# yetisponder_vesp02_2_1.net
KiCad netlist of a schematic drawn in EAGLE
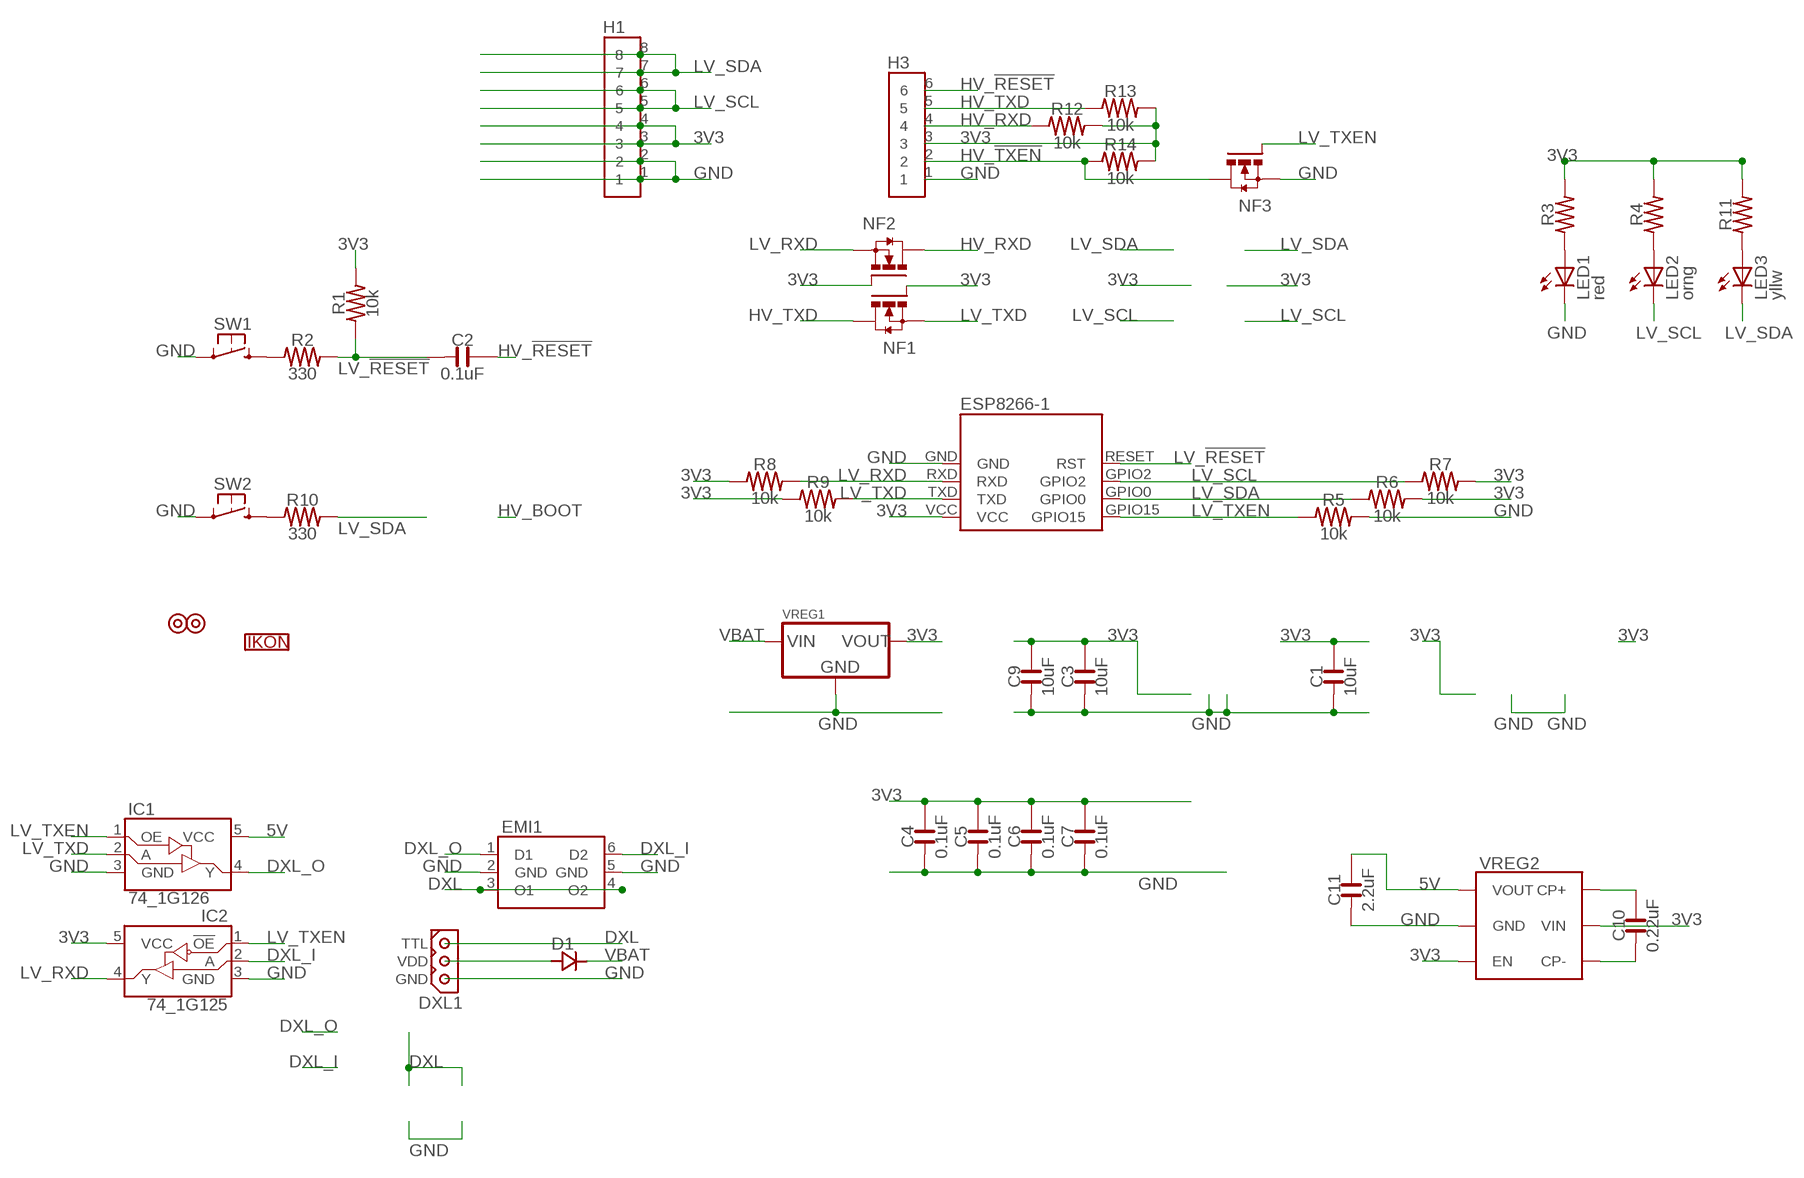
[diagram p0: schematic, sheet 1]

(export (version "E")
  (design (tool "Eeschema 10.0.6"))
  (components
    (comp (ref "C1")
      (value "10uF")
      (footprint "eagle-import:0805_YAGEO")
      (libsource (lib "eagle-import") (part "CAPACITOR-0805"))
    )
    (comp (ref "C2")
      (value "0.1uF")
      (footprint "eagle-import:0402_YAGEO")
      (libsource (lib "eagle-import") (part "CAPACITOR-0402"))
    )
    (comp (ref "C3")
      (value "10uF")
      (footprint "eagle-import:0805_YAGEO")
      (libsource (lib "eagle-import") (part "CAPACITOR-0805"))
    )
    (comp (ref "C4")
      (value "0.1uF")
      (footprint "eagle-import:0402_YAGEO")
      (libsource (lib "eagle-import") (part "CAPACITOR-0402"))
    )
    (comp (ref "C5")
      (value "0.1uF")
      (footprint "eagle-import:0402_YAGEO")
      (libsource (lib "eagle-import") (part "CAPACITOR-0402"))
    )
    (comp (ref "C6")
      (value "0.1uF")
      (footprint "eagle-import:0402_YAGEO")
      (libsource (lib "eagle-import") (part "CAPACITOR-0402"))
    )
    (comp (ref "C7")
      (value "0.1uF")
      (footprint "eagle-import:0402_YAGEO")
      (libsource (lib "eagle-import") (part "CAPACITOR-0402"))
    )
    (comp (ref "C9")
      (value "10uF")
      (footprint "eagle-import:0805_YAGEO")
      (libsource (lib "eagle-import") (part "CAPACITOR-0805"))
    )
    (comp (ref "C10")
      (value "0.22uF")
      (footprint "eagle-import:0402_YAGEO")
      (libsource (lib "eagle-import") (part "CAPACITOR-0402"))
    )
    (comp (ref "C11")
      (value "2.2uF")
      (footprint "eagle-import:0402_YAGEO")
      (libsource (lib "eagle-import") (part "CAPACITOR-0402"))
    )
    (comp (ref "D1")
      (value "DIODE_RECTIFIER-POWER-DI5")
      (footprint "eagle-import:POWER-DI5")
      (libsource (lib "eagle-import") (part "DIODE_RECTIFIER-POWER-DI5"))
    )
    (comp (ref "DXL1")
      (value "DXL_TTL-V")
      (footprint "eagle-import:MOLEX_5267-3")
      (libsource (lib "eagle-import") (part "DXL_TTL-V"))
    )
    (comp (ref "EMI1")
      (value "EMI_2CH")
      (footprint "eagle-import:SOT-563")
      (libsource (lib "eagle-import") (part "EMI_2CH"))
    )
    (comp (ref "ESP8266-1")
      (value "ESP8266-02")
      (footprint "eagle-import:ESP8266-02")
      (libsource (lib "eagle-import") (part "ESP8266-02"))
    )
    (comp (ref "H1")
      (value "HEADER_8P-0.1\"_2X4-SMD-SULLINS")
      (footprint "eagle-import:HEADER-0.1__2X4-SMD-SULLINS")
      (libsource (lib "eagle-import") (part "HEADER_8P-0.1{dblquote}_2X4-SMD-SULLINS"))
    )
    (comp (ref "H3")
      (value "HEADER_6P-0.1\"")
      (footprint "eagle-import:HEADER-0.1__1X6")
      (libsource (lib "eagle-import") (part "HEADER_6P-0.1{dblquote}"))
    )
    (comp (ref "IC1")
      (value "LOGIC_74_1G126-DCK")
      (footprint "eagle-import:DCK(R-PDSO-G5)_SC70")
      (libsource (lib "eagle-import") (part "LOGIC_74_1G126-DCK"))
    )
    (comp (ref "IC2")
      (value "LOGIC_74_1G125-DCK")
      (footprint "eagle-import:DCK(R-PDSO-G5)_SC70")
      (libsource (lib "eagle-import") (part "LOGIC_74_1G125-DCK"))
    )
    (comp (ref "IKON1")
      (value "IKON-VERSACOMA-5")
      (footprint "eagle-import:IKON_VERSACOMA_5MM")
      (libsource (lib "eagle-import") (part "IKON-VERSACOMA-5"))
    )
    (comp (ref "LED1")
      (value "red")
      (footprint "eagle-import:0402_LED")
      (libsource (lib "eagle-import") (part "LED-0402"))
    )
    (comp (ref "LED2")
      (value "orng")
      (footprint "eagle-import:0402_LED")
      (libsource (lib "eagle-import") (part "LED-0402"))
    )
    (comp (ref "LED3")
      (value "yllw")
      (footprint "eagle-import:0402_LED")
      (libsource (lib "eagle-import") (part "LED-0402"))
    )
    (comp (ref "NF1")
      (value "FET_N-CH-SOT-23-3")
      (footprint "eagle-import:SOT-23-3")
      (libsource (lib "eagle-import") (part "FET_N-CH-SOT-23-3"))
    )
    (comp (ref "NF2")
      (value "FET_N-CH-SOT-23-3")
      (footprint "eagle-import:SOT-23-3")
      (libsource (lib "eagle-import") (part "FET_N-CH-SOT-23-3"))
    )
    (comp (ref "NF3")
      (value "FET_N-CH-SOT-23-3")
      (footprint "eagle-import:SOT-23-3")
      (libsource (lib "eagle-import") (part "FET_N-CH-SOT-23-3"))
    )
    (comp (ref "R1")
      (value "10k")
      (footprint "eagle-import:0402_YAGEO")
      (libsource (lib "eagle-import") (part "RESISTOR-0402"))
    )
    (comp (ref "R2")
      (value "330")
      (footprint "eagle-import:0402_YAGEO")
      (libsource (lib "eagle-import") (part "RESISTOR-0402"))
    )
    (comp (ref "R3")
      (value "RESISTOR-0402")
      (footprint "eagle-import:0402_YAGEO")
      (libsource (lib "eagle-import") (part "RESISTOR-0402"))
    )
    (comp (ref "R4")
      (value "RESISTOR-0402")
      (footprint "eagle-import:0402_YAGEO")
      (libsource (lib "eagle-import") (part "RESISTOR-0402"))
    )
    (comp (ref "R5")
      (value "10k")
      (footprint "eagle-import:0402_YAGEO")
      (libsource (lib "eagle-import") (part "RESISTOR-0402"))
    )
    (comp (ref "R6")
      (value "10k")
      (footprint "eagle-import:0402_YAGEO")
      (libsource (lib "eagle-import") (part "RESISTOR-0402"))
    )
    (comp (ref "R7")
      (value "10k")
      (footprint "eagle-import:0402_YAGEO")
      (libsource (lib "eagle-import") (part "RESISTOR-0402"))
    )
    (comp (ref "R8")
      (value "10k")
      (footprint "eagle-import:0402_YAGEO")
      (libsource (lib "eagle-import") (part "RESISTOR-0402"))
    )
    (comp (ref "R9")
      (value "10k")
      (footprint "eagle-import:0402_YAGEO")
      (libsource (lib "eagle-import") (part "RESISTOR-0402"))
    )
    (comp (ref "R10")
      (value "330")
      (footprint "eagle-import:0402_YAGEO")
      (libsource (lib "eagle-import") (part "RESISTOR-0402"))
    )
    (comp (ref "R11")
      (value "RESISTOR-0402")
      (footprint "eagle-import:0402_YAGEO")
      (libsource (lib "eagle-import") (part "RESISTOR-0402"))
    )
    (comp (ref "R12")
      (value "10k")
      (footprint "eagle-import:0402_YAGEO")
      (libsource (lib "eagle-import") (part "RESISTOR-0402"))
    )
    (comp (ref "R13")
      (value "10k")
      (footprint "eagle-import:0402_YAGEO")
      (libsource (lib "eagle-import") (part "RESISTOR-0402"))
    )
    (comp (ref "R14")
      (value "10k")
      (footprint "eagle-import:0402_YAGEO")
      (libsource (lib "eagle-import") (part "RESISTOR-0402"))
    )
    (comp (ref "S1")
      (value "METRIC_SCREWS-M2.5_T")
      (footprint "eagle-import:M2.5_SCREW_TENTED")
      (libsource (lib "eagle-import") (part "METRIC_SCREWS-M2.5_T"))
    )
    (comp (ref "S2")
      (value "METRIC_SCREWS-M2.5_T")
      (footprint "eagle-import:M2.5_SCREW_TENTED")
      (libsource (lib "eagle-import") (part "METRIC_SCREWS-M2.5_T"))
    )
    (comp (ref "SW1")
      (value "SWITCH_SPST-6MMX6MM-PTH")
      (footprint "eagle-import:SWITCH_TE_1825910-7")
      (libsource (lib "eagle-import") (part "SWITCH_SPST-6MMX6MM-PTH"))
    )
    (comp (ref "SW2")
      (value "SWITCH_SPST-6MMX6MM-PTH")
      (footprint "eagle-import:SWITCH_TE_1825910-7")
      (libsource (lib "eagle-import") (part "SWITCH_SPST-6MMX6MM-PTH"))
    )
    (comp (ref "VREG1")
      (value "VREG_78XX-OKI-78SR-H")
      (footprint "eagle-import:VREG-OKI-78SR-H")
      (libsource (lib "eagle-import") (part "VREG_78XX-OKI-78SR-H"))
    )
    (comp (ref "VREG2")
      (value "VREG_REG710XX")
      (footprint "eagle-import:SOT-23-6")
      (libsource (lib "eagle-import") (part "VREG_REG710XX"))
    )
  )
  (nets
    (net (code "1") (name "/3V3") (class "Default")
      (node (ref "C1") (pin "2") (pinfunction "P$2_2") (pintype "passive"))
      (node (ref "C3") (pin "2") (pinfunction "P$2_2") (pintype "passive"))
      (node (ref "C4") (pin "2") (pinfunction "P$2_2") (pintype "passive"))
      (node (ref "C5") (pin "2") (pinfunction "P$2_2") (pintype "passive"))
      (node (ref "C6") (pin "2") (pinfunction "P$2_2") (pintype "passive"))
      (node (ref "C7") (pin "2") (pinfunction "P$2_2") (pintype "passive"))
      (node (ref "C9") (pin "2") (pinfunction "P$2_2") (pintype "passive"))
      (node (ref "ESP8266-1") (pin "VCC") (pinfunction "VCC_VCC") (pintype "bidirectional"))
      (node (ref "H1") (pin "3") (pinfunction "3_3") (pintype "bidirectional"))
      (node (ref "H1") (pin "4") (pinfunction "4_4") (pintype "bidirectional"))
      (node (ref "H3") (pin "3") (pinfunction "3_3") (pintype "bidirectional"))
      (node (ref "IC2") (pin "5") (pinfunction "VCC_5") (pintype "bidirectional"))
      (node (ref "NF1") (pin "1G") (pinfunction "G_1G") (pintype "passive"))
      (node (ref "NF2") (pin "1G") (pinfunction "G_1G") (pintype "passive"))
      (node (ref "R1") (pin "2") (pinfunction "2_2") (pintype "passive"))
      (node (ref "R11") (pin "2") (pinfunction "2_2") (pintype "passive"))
      (node (ref "R12") (pin "2") (pinfunction "2_2") (pintype "passive"))
      (node (ref "R13") (pin "2") (pinfunction "2_2") (pintype "passive"))
      (node (ref "R14") (pin "2") (pinfunction "2_2") (pintype "passive"))
      (node (ref "R3") (pin "2") (pinfunction "2_2") (pintype "passive"))
      (node (ref "R4") (pin "2") (pinfunction "2_2") (pintype "passive"))
      (node (ref "R6") (pin "2") (pinfunction "2_2") (pintype "passive"))
      (node (ref "R7") (pin "2") (pinfunction "2_2") (pintype "passive"))
      (node (ref "R8") (pin "1") (pinfunction "1_1") (pintype "passive"))
      (node (ref "R9") (pin "1") (pinfunction "1_1") (pintype "passive"))
      (node (ref "VREG1") (pin "3") (pinfunction "VOUT_3") (pintype "bidirectional"))
      (node (ref "VREG2") (pin "3") (pinfunction "EN_3") (pintype "bidirectional"))
      (node (ref "VREG2") (pin "5") (pinfunction "VIN_5") (pintype "bidirectional"))
    )
    (net (code "2") (name "/5V") (class "Default")
      (node (ref "C11") (pin "2") (pinfunction "P$2_2") (pintype "passive"))
      (node (ref "IC1") (pin "5") (pinfunction "VCC_5") (pintype "bidirectional"))
      (node (ref "VREG2") (pin "1") (pinfunction "VOUT_1") (pintype "bidirectional"))
    )
    (net (code "3") (name "/DXL") (class "Default")
      (node (ref "DXL1") (pin "1") (pinfunction "TTL_1") (pintype "bidirectional"))
      (node (ref "EMI1") (pin "3") (pinfunction "O1_3") (pintype "bidirectional"))
      (node (ref "EMI1") (pin "4") (pinfunction "O2_4") (pintype "bidirectional"))
    )
    (net (code "4") (name "/DXL_I") (class "Default")
      (node (ref "EMI1") (pin "6") (pinfunction "D2_6") (pintype "bidirectional"))
      (node (ref "IC2") (pin "2") (pinfunction "A_2") (pintype "bidirectional"))
    )
    (net (code "5") (name "/DXL_O") (class "Default")
      (node (ref "EMI1") (pin "1") (pinfunction "D1_1") (pintype "bidirectional"))
      (node (ref "IC1") (pin "4") (pinfunction "Y_4") (pintype "bidirectional"))
    )
    (net (code "6") (name "/GND") (class "Default")
      (node (ref "C1") (pin "1") (pinfunction "P$1_1") (pintype "passive"))
      (node (ref "C11") (pin "1") (pinfunction "P$1_1") (pintype "passive"))
      (node (ref "C3") (pin "1") (pinfunction "P$1_1") (pintype "passive"))
      (node (ref "C4") (pin "1") (pinfunction "P$1_1") (pintype "passive"))
      (node (ref "C5") (pin "1") (pinfunction "P$1_1") (pintype "passive"))
      (node (ref "C6") (pin "1") (pinfunction "P$1_1") (pintype "passive"))
      (node (ref "C7") (pin "1") (pinfunction "P$1_1") (pintype "passive"))
      (node (ref "C9") (pin "1") (pinfunction "P$1_1") (pintype "passive"))
      (node (ref "DXL1") (pin "3") (pinfunction "GND_3") (pintype "bidirectional"))
      (node (ref "EMI1") (pin "2") (pinfunction "GND_2") (pintype "bidirectional"))
      (node (ref "EMI1") (pin "5") (pinfunction "GND_5") (pintype "bidirectional"))
      (node (ref "ESP8266-1") (pin "GND") (pinfunction "GND_GND") (pintype "bidirectional"))
      (node (ref "H1") (pin "1") (pinfunction "1_1") (pintype "bidirectional"))
      (node (ref "H1") (pin "2") (pinfunction "2_2") (pintype "bidirectional"))
      (node (ref "H3") (pin "1") (pinfunction "1_1") (pintype "bidirectional"))
      (node (ref "IC1") (pin "3") (pinfunction "GND_3") (pintype "bidirectional"))
      (node (ref "IC2") (pin "3") (pinfunction "GND_3") (pintype "bidirectional"))
      (node (ref "LED1") (pin "C") (pinfunction "C_C") (pintype "passive"))
      (node (ref "NF3") (pin "2S") (pinfunction "S_2S") (pintype "passive"))
      (node (ref "R5") (pin "2") (pinfunction "2_2") (pintype "passive"))
      (node (ref "SW1") (pin "2@1") (pinfunction "2_2@1") (pintype "passive"))
      (node (ref "SW1") (pin "2@2") (pinfunction "2_2@2") (pintype "passive"))
      (node (ref "SW2") (pin "2@1") (pinfunction "2_2@1") (pintype "passive"))
      (node (ref "SW2") (pin "2@2") (pinfunction "2_2@2") (pintype "passive"))
      (node (ref "VREG1") (pin "2") (pinfunction "GND_2") (pintype "bidirectional"))
      (node (ref "VREG2") (pin "2") (pinfunction "GND_2") (pintype "bidirectional"))
    )
    (net (code "8") (name "/HV_RXD") (class "Default")
      (node (ref "H3") (pin "4") (pinfunction "4_4") (pintype "bidirectional"))
      (node (ref "NF2") (pin "3D") (pinfunction "D_3D") (pintype "passive"))
      (node (ref "R12") (pin "1") (pinfunction "1_1") (pintype "passive"))
    )
    (net (code "9") (name "/HV_TXD") (class "Default")
      (node (ref "H3") (pin "5") (pinfunction "5_5") (pintype "bidirectional"))
      (node (ref "NF1") (pin "3D") (pinfunction "D_3D") (pintype "passive"))
      (node (ref "R13") (pin "1") (pinfunction "1_1") (pintype "passive"))
    )
    (net (code "10") (name "/HV_~{RESET}") (class "Default")
      (node (ref "C2") (pin "2") (pinfunction "P$2_2") (pintype "passive"))
      (node (ref "H3") (pin "6") (pinfunction "6_6") (pintype "bidirectional"))
    )
    (net (code "11") (name "/HV_~{TXEN}") (class "Default")
      (node (ref "H3") (pin "2") (pinfunction "2_2") (pintype "bidirectional"))
      (node (ref "NF3") (pin "3D") (pinfunction "D_3D") (pintype "passive"))
      (node (ref "R14") (pin "1") (pinfunction "1_1") (pintype "passive"))
    )
    (net (code "12") (name "/LV_RXD") (class "Default")
      (node (ref "ESP8266-1") (pin "RXD") (pinfunction "RXD_RXD") (pintype "bidirectional"))
      (node (ref "IC2") (pin "4") (pinfunction "Y_4") (pintype "bidirectional"))
      (node (ref "NF2") (pin "2S") (pinfunction "S_2S") (pintype "passive"))
      (node (ref "R8") (pin "2") (pinfunction "2_2") (pintype "passive"))
    )
    (net (code "13") (name "/LV_SCL") (class "Default")
      (node (ref "ESP8266-1") (pin "GPIO2") (pinfunction "GPIO2_GPIO2") (pintype "bidirectional"))
      (node (ref "H1") (pin "5") (pinfunction "5_5") (pintype "bidirectional"))
      (node (ref "H1") (pin "6") (pinfunction "6_6") (pintype "bidirectional"))
      (node (ref "LED2") (pin "C") (pinfunction "C_C") (pintype "passive"))
      (node (ref "R7") (pin "1") (pinfunction "1_1") (pintype "passive"))
    )
    (net (code "14") (name "/LV_SDA") (class "Default")
      (node (ref "ESP8266-1") (pin "GPIO0") (pinfunction "GPIO0_GPIO0") (pintype "bidirectional"))
      (node (ref "H1") (pin "7") (pinfunction "7_7") (pintype "bidirectional"))
      (node (ref "H1") (pin "8") (pinfunction "8_8") (pintype "bidirectional"))
      (node (ref "LED3") (pin "C") (pinfunction "C_C") (pintype "passive"))
      (node (ref "R10") (pin "2") (pinfunction "2_2") (pintype "passive"))
      (node (ref "R6") (pin "1") (pinfunction "1_1") (pintype "passive"))
    )
    (net (code "15") (name "/LV_TXD") (class "Default")
      (node (ref "ESP8266-1") (pin "TXD") (pinfunction "TXD_TXD") (pintype "bidirectional"))
      (node (ref "IC1") (pin "2") (pinfunction "A_2") (pintype "bidirectional"))
      (node (ref "NF1") (pin "2S") (pinfunction "S_2S") (pintype "passive"))
      (node (ref "R9") (pin "2") (pinfunction "2_2") (pintype "passive"))
    )
    (net (code "16") (name "/LV_TXEN") (class "Default")
      (node (ref "ESP8266-1") (pin "GPIO15") (pinfunction "GPIO15_GPIO15") (pintype "bidirectional"))
      (node (ref "IC1") (pin "1") (pinfunction "OE_1") (pintype "bidirectional"))
      (node (ref "IC2") (pin "1") (pinfunction "~{OE}_1") (pintype "bidirectional"))
      (node (ref "NF3") (pin "1G") (pinfunction "G_1G") (pintype "passive"))
      (node (ref "R5") (pin "1") (pinfunction "1_1") (pintype "passive"))
    )
    (net (code "17") (name "/LV_~{RESET}") (class "Default")
      (node (ref "C2") (pin "1") (pinfunction "P$1_1") (pintype "passive"))
      (node (ref "ESP8266-1") (pin "RESET") (pinfunction "RST_RESET") (pintype "bidirectional"))
      (node (ref "R1") (pin "1") (pinfunction "1_1") (pintype "passive"))
      (node (ref "R2") (pin "2") (pinfunction "2_2") (pintype "passive"))
    )
    (net (code "18") (name "/VBAT") (class "Default")
      (node (ref "D1") (pin "PAD") (pinfunction "C_PAD") (pintype "bidirectional"))
      (node (ref "VREG1") (pin "1") (pinfunction "VIN_1") (pintype "bidirectional"))
    )
    (net (code "19") (name "Net-(C10-P$1)") (class "Default")
      (node (ref "C10") (pin "1") (pinfunction "P$1_1") (pintype "passive"))
      (node (ref "VREG2") (pin "4") (pinfunction "CP-_4") (pintype "bidirectional"))
    )
    (net (code "20") (name "Net-(C10-P$2)") (class "Default")
      (node (ref "C10") (pin "2") (pinfunction "P$2_2") (pintype "passive"))
      (node (ref "VREG2") (pin "6") (pinfunction "CP+_6") (pintype "bidirectional"))
    )
    (net (code "21") (name "Net-(DXL1-VDD)") (class "Default")
      (node (ref "D1") (pin "LEFT") (pinfunction "A_LEFT") (pintype "bidirectional"))
      (node (ref "D1") (pin "RIGHT") (pinfunction "A_RIGHT") (pintype "bidirectional"))
      (node (ref "DXL1") (pin "2") (pinfunction "VDD_2") (pintype "bidirectional"))
    )
    (net (code "22") (name "Net-(LED1-PadA)") (class "Default")
      (node (ref "LED1") (pin "A") (pinfunction "A_A") (pintype "passive"))
      (node (ref "R3") (pin "1") (pinfunction "1_1") (pintype "passive"))
    )
    (net (code "23") (name "Net-(LED2-PadA)") (class "Default")
      (node (ref "LED2") (pin "A") (pinfunction "A_A") (pintype "passive"))
      (node (ref "R4") (pin "1") (pinfunction "1_1") (pintype "passive"))
    )
    (net (code "24") (name "Net-(LED3-PadA)") (class "Default")
      (node (ref "LED3") (pin "A") (pinfunction "A_A") (pintype "passive"))
      (node (ref "R11") (pin "1") (pinfunction "1_1") (pintype "passive"))
    )
    (net (code "25") (name "Net-(R2-Pad1)") (class "Default")
      (node (ref "R2") (pin "1") (pinfunction "1_1") (pintype "passive"))
      (node (ref "SW1") (pin "1@1") (pinfunction "1_1@1") (pintype "passive"))
      (node (ref "SW1") (pin "1@2") (pinfunction "1_1@2") (pintype "passive"))
    )
    (net (code "26") (name "Net-(R10-Pad1)") (class "Default")
      (node (ref "R10") (pin "1") (pinfunction "1_1") (pintype "passive"))
      (node (ref "SW2") (pin "1@1") (pinfunction "1_1@1") (pintype "passive"))
      (node (ref "SW2") (pin "1@2") (pinfunction "1_1@2") (pintype "passive"))
    )
    (net (code "27") (name "unconnected-(S1-PadP$1)") (class "Default")
      (node (ref "S1") (pin "P$1") (pinfunction "P$1_P$1") (pintype "passive"))
    )
    (net (code "28") (name "unconnected-(S2-PadP$1)") (class "Default")
      (node (ref "S2") (pin "P$1") (pinfunction "P$1_P$1") (pintype "passive"))
    )
  )
)
